# Sheet1.net
KiCad netlist of a schematic drawn in Altium Designer
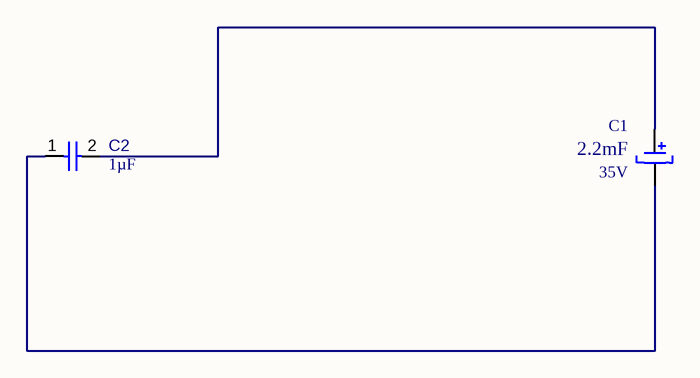
[diagram p0: Sheet1.SchDoc]

(export (version "E")
  (design (tool "Eeschema 10.0.6"))
  (components
    (comp (ref "C1")
      (value "2.2mF")
      (footprint "alum16_t2_d1650_0_h2700_G")
      (description "CAPACITOR, ALUMINUM, 2.2 MF, 20 PERCENTAGE , 35.0 V, THD, D:16, (LF), (A), P1")
      (fields
        (field (name "RATED VOLTAGE") "35V")
        (field (name "TOLERANCE") "0.2%")
        (field (name "PART NUMBER") "609837000A")
        (field (name "AUTHORITY") "105218 AHO GPM EL CO")
        (field (name "CREATED BY ECR") "214849")
      )
      (libsource (lib "AES (OnPrem-QA2)") (part "ELECTROLYTIC"))
    )
    (comp (ref "C2")
      (value "1µF")
      (footprint "CAPC2013X145X50ML20T25")
      (description "Chip Capacitor, 1 uF, +/-10%, 25 V, 0805 (2012 Metric)")
      (fields (field (name "TOLERANCE") "10%") (field (name "Comment") "Capacitor 1 uF +/- 10% 25 V 0805"))
      (libsource (lib "✦✦✦Customization✦✦✦") (part "CAP-NP-2"))
    )
  )
  (nets
    (net (code "1") (name "Net-(C1-m)") (class "Default")
      (node (ref "C1") (pin "2") (pinfunction "m_2") (pintype "passive"))
      (node (ref "C2") (pin "1") (pinfunction "1_1") (pintype "passive"))
    )
    (net (code "2") (name "Net-(C1-p)") (class "Default")
      (node (ref "C1") (pin "1") (pinfunction "p_1") (pintype "passive"))
      (node (ref "C2") (pin "2") (pinfunction "2_2") (pintype "passive"))
    )
  )
)
